# dainyuan.net
KiCad netlist of a schematic drawn in Altium Designer
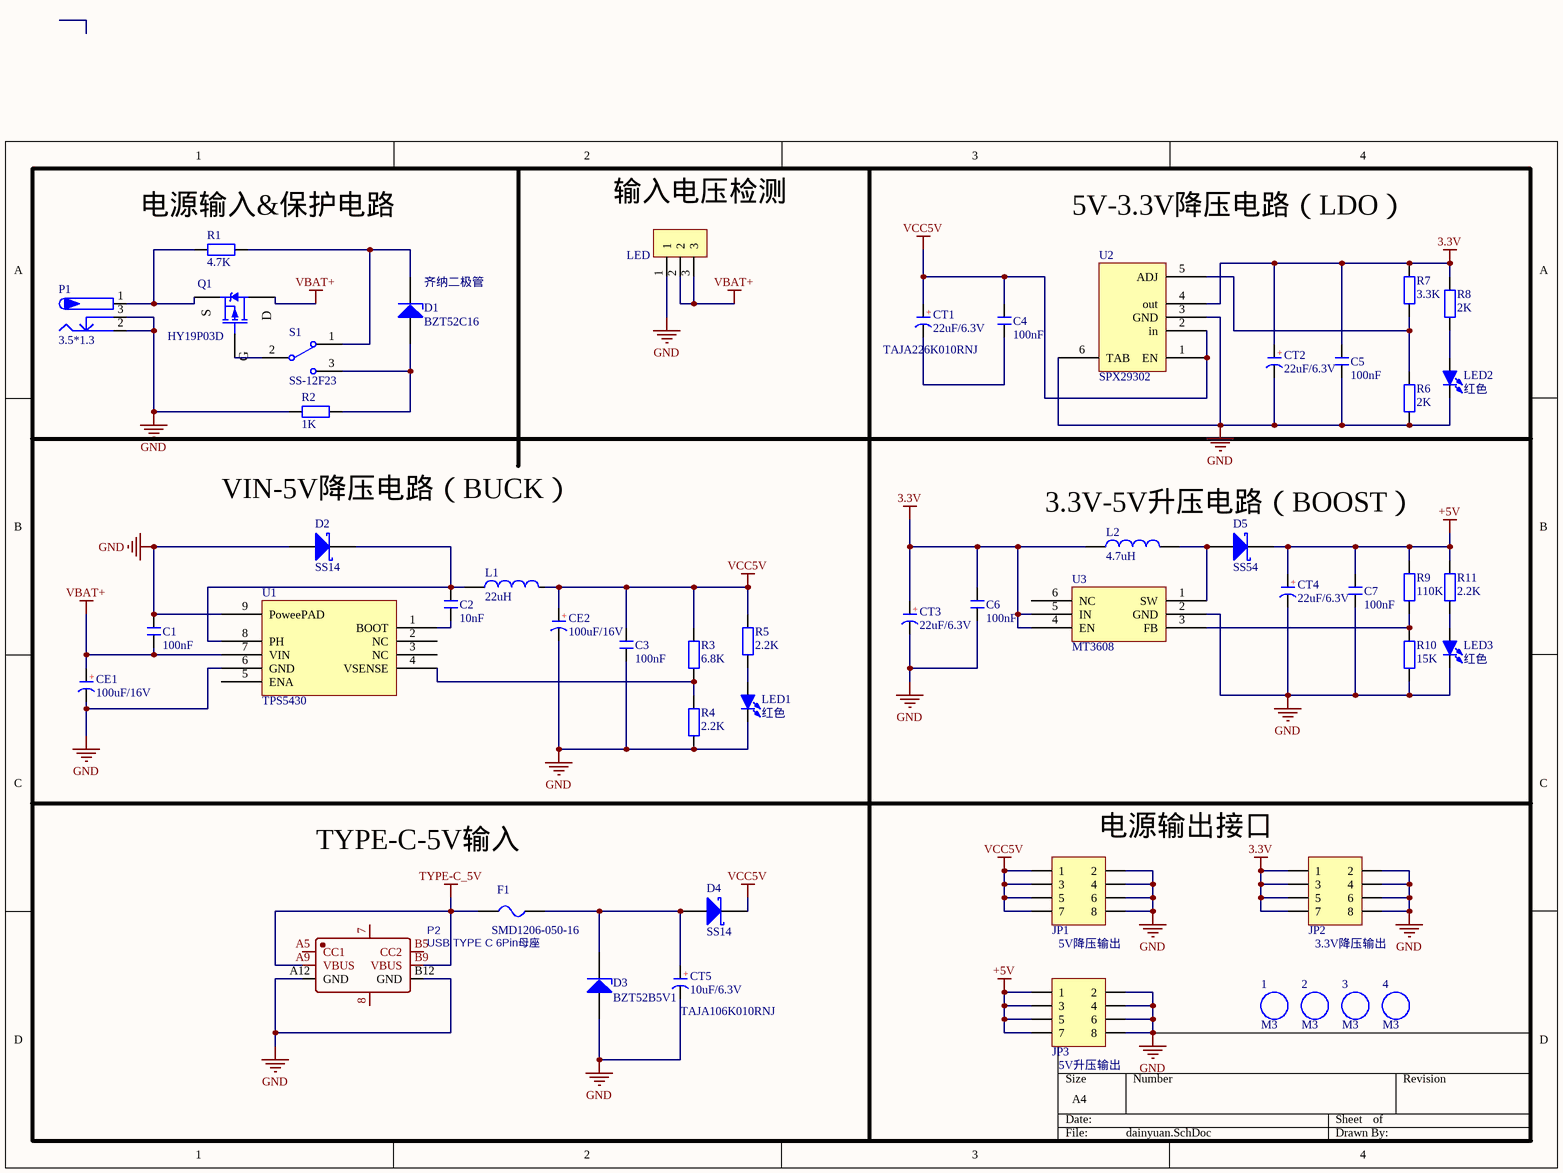
[diagram p0: dainyuan.SchDoc]

(export (version "E")
  (design (tool "Eeschema 10.0.6"))
  (components
    (comp (ref "1")
      (value "M3")
      (footprint "M3 125X200")
      (description "铜柱孔")
      (libsource (lib "0.7 - 常用按键-开关-蜂鸣器-电池") (part "M3"))
    )
    (comp (ref "2")
      (value "M3")
      (footprint "M3 125X200")
      (description "铜柱孔")
      (libsource (lib "0.7 - 常用按键-开关-蜂鸣器-电池") (part "M3"))
    )
    (comp (ref "3")
      (value "M3")
      (footprint "M3 125X200")
      (description "铜柱孔")
      (libsource (lib "0.7 - 常用按键-开关-蜂鸣器-电池") (part "M3"))
    )
    (comp (ref "4")
      (value "M3")
      (footprint "M3 125X200")
      (description "铜柱孔")
      (libsource (lib "0.7 - 常用按键-开关-蜂鸣器-电池") (part "M3"))
    )
    (comp (ref "C1")
      (value "100nF")
      (footprint "C 0805_L")
      (description "贴片电容")
      (libsource (lib "0.1 - 电阻-电容-电感") (part "C"))
    )
    (comp (ref "C2")
      (value "10nF")
      (footprint "C 0805_L")
      (description "贴片电容")
      (libsource (lib "0.1 - 电阻-电容-电感") (part "C"))
    )
    (comp (ref "C3")
      (value "100nF")
      (footprint "C 0805_L")
      (description "贴片电容")
      (libsource (lib "0.1 - 电阻-电容-电感") (part "C"))
    )
    (comp (ref "C4")
      (value "100nF")
      (footprint "C 0805_L")
      (description "贴片电容")
      (libsource (lib "0.1 - 电阻-电容-电感") (part "C"))
    )
    (comp (ref "C5")
      (value "100nF")
      (footprint "C 0805_L")
      (description "贴片电容")
      (libsource (lib "0.1 - 电阻-电容-电感") (part "C"))
    )
    (comp (ref "C6")
      (value "100nF")
      (footprint "C 0805_L")
      (description "贴片电容")
      (libsource (lib "0.1 - 电阻-电容-电感") (part "C"))
    )
    (comp (ref "C7")
      (value "100nF")
      (footprint "C 0805_L")
      (description "贴片电容")
      (libsource (lib "0.1 - 电阻-电容-电感") (part "C"))
    )
    (comp (ref "CE1")
      (value "100uF/16V")
      (footprint "CAP 3.5*8*11.5 - BK")
      (description "直插电解电容")
      (libsource (lib "0.1 - 电阻-电容-电感") (part "CE"))
    )
    (comp (ref "CE2")
      (value "100uF/16V")
      (footprint "CAP 3.5*8*11.5 - BK")
      (description "直插电解电容")
      (libsource (lib "0.1 - 电阻-电容-电感") (part "CE"))
    )
    (comp (ref "CT1")
      (value "22uF/6.3V")
      (footprint "CD A(3216)")
      (description "贴片钽电容")
      (libsource (lib "0.1 - 电阻-电容-电感") (part "CT"))
    )
    (comp (ref "CT2")
      (value "22uF/6.3V")
      (footprint "CD A(3216)")
      (description "贴片钽电容")
      (libsource (lib "0.1 - 电阻-电容-电感") (part "CT"))
    )
    (comp (ref "CT3")
      (value "22uF/6.3V")
      (footprint "CD A(3216)")
      (description "贴片钽电容")
      (libsource (lib "0.1 - 电阻-电容-电感") (part "CT"))
    )
    (comp (ref "CT4")
      (value "22uF/6.3V")
      (footprint "CD A(3216)")
      (description "贴片钽电容")
      (libsource (lib "0.1 - 电阻-电容-电感") (part "CT"))
    )
    (comp (ref "CT5")
      (value "10uF/6.3V")
      (footprint "CD A(3216)")
      (description "贴片钽电容")
      (libsource (lib "0.1 - 电阻-电容-电感") (part "CT"))
    )
    (comp (ref "D1")
      (value "BZT52C16")
      (footprint "SOD-123")
      (description "Zener Diode（齐纳）")
      (libsource (lib "0.2 - 二极管-整流桥") (part "稳压二极管"))
    )
    (comp (ref "D2")
      (value "SS14")
      (footprint "SMA")
      (description "肖特基二极管")
      (libsource (lib "0.2 - 二极管-整流桥") (part "SS14"))
    )
    (comp (ref "D3")
      (value "BZT52B5V1")
      (footprint "SOD-123")
      (description "Zener Diode")
      (libsource (lib "0.2 - 二极管-整流桥") (part "稳压二极管"))
    )
    (comp (ref "D4")
      (value "SS14")
      (footprint "SMA")
      (description "肖特基二极管")
      (libsource (lib "0.2 - 二极管-整流桥") (part "SS14"))
    )
    (comp (ref "D5")
      (value "SS54")
      (footprint "SMB")
      (description "肖特基二极管")
      (libsource (lib "0.2 - 二极管-整流桥") (part "SS54"))
    )
    (comp (ref "F1")
      (value "SMD1206-050-16")
      (footprint "FU 1206")
      (description "自恢复保险丝")
      (fields (field (name "版权归属") "封装库来自淘宝卖家 ID：黄晶宝石"))
      (libsource (lib "0.5 - 保险丝-晶振-光耦") (part "FU"))
    )
    (comp (ref "JP1")
      (value "Header 4X2")
      (footprint "HDR2.54-LI-2x4P")
      (description "4*2P接插件")
      (fields (field (name "版权归属") "封装库来自淘宝 ID：黄晶宝石"))
      (libsource (lib "5.4 - 接插件-脚距2.54 (100mil) ") (part "Header 4X2"))
    )
    (comp (ref "JP2")
      (value "Header 4X2")
      (footprint "HDR2.54-LI-2x4P")
      (description "4*2P接插件")
      (fields (field (name "版权归属") "封装库来自淘宝 ID：黄晶宝石"))
      (libsource (lib "5.4 - 接插件-脚距2.54 (100mil) ") (part "Header 4X2"))
    )
    (comp (ref "JP3")
      (value "Header 4X2")
      (footprint "HDR2.54-LI-2x4P")
      (description "4*2P接插件")
      (fields (field (name "版权归属") "封装库来自淘宝 ID：黄晶宝石"))
      (libsource (lib "5.4 - 接插件-脚距2.54 (100mil) ") (part "Header 4X2"))
    )
    (comp (ref "L1")
      (value "22uH")
      (footprint "L-SMD-0630")
      (description "小功率贴片电感")
      (libsource (lib "0.1 - 电阻-电容-电感") (part "L"))
    )
    (comp (ref "L2")
      (value "4.7uH")
      (footprint "L-SMD-0630")
      (description "小功率贴片电感")
      (libsource (lib "0.1 - 电阻-电容-电感") (part "L"))
    )
    (comp (ref "LED")
      (value "HDR-1X3")
      (footprint "HDR2.54-M-LI-3P")
      (description "3P接插件")
      (fields (field (name "版权归属") "封装库来自淘宝 ID：黄晶宝石"))
      (libsource (lib "5.4 - 接插件-脚距2.54 (100mil) ") (part "Header 3"))
    )
    (comp (ref "LED1")
      (value "红色")
      (footprint "LED 0805R")
      (description "贴片LED")
      (libsource (lib "0.3 - LED发光二极管") (part "LED-SMD"))
    )
    (comp (ref "LED2")
      (value "红色")
      (footprint "LED 0805R")
      (description "贴片LED")
      (libsource (lib "0.3 - LED发光二极管") (part "LED-SMD"))
    )
    (comp (ref "LED3")
      (value "红色")
      (footprint "LED 0805R")
      (description "贴片LED")
      (libsource (lib "0.3 - LED发光二极管") (part "LED-SMD"))
    )
    (comp (ref "P1")
      (value "3.5*1.3")
      (footprint "DC-005")
      (description "低压电源接口")
      (fields (field (name "版权归属") "封装库来自淘宝 ID：黄晶宝石"))
      (libsource (lib "0.8 - 以太网-音频-USB插座") (part "P-DC"))
    )
    (comp (ref "P2")
      (value "USB TYPE C 6Pin母座")
      (footprint "USB-C-SMD_10P-P1.00-L6.8-W8.9")
      (fields
        (field (name "BOM_SUPPLIER PART") "C381473")
        (field (name "BOM_MANUFACTURER PART") "TYC-252D-CB160")
        (field (name "CONTRIBUTOR") "LCSC")
      )
      (libsource (lib "0.8 - 以太网-音频-USB插座") (part "USB TYPE C 6Pin母座"))
    )
    (comp (ref "Q1")
      (value "HY19P03D")
      (footprint "TO252 - 3")
      (description "P沟场效应管")
      (libsource (lib "0.4 - 三极管-场效应管-可控硅") (part "IRF540"))
    )
    (comp (ref "R1")
      (value "4.7K")
      (footprint "R 0805_L")
      (description "贴片电阻")
      (libsource (lib "0.1 - 电阻-电容-电感") (part "R"))
    )
    (comp (ref "R2")
      (value "1K")
      (footprint "R 0805_L")
      (description "贴片电阻")
      (libsource (lib "0.1 - 电阻-电容-电感") (part "R"))
    )
    (comp (ref "R3")
      (value "6.8K")
      (footprint "R 0805_L")
      (description "贴片电阻")
      (libsource (lib "0.1 - 电阻-电容-电感") (part "R"))
    )
    (comp (ref "R4")
      (value "2.2K")
      (footprint "R 0805_L")
      (description "贴片电阻")
      (libsource (lib "0.1 - 电阻-电容-电感") (part "R"))
    )
    (comp (ref "R5")
      (value "2.2K")
      (footprint "R 0805_L")
      (description "贴片电阻")
      (libsource (lib "0.1 - 电阻-电容-电感") (part "R"))
    )
    (comp (ref "R6")
      (value "2K")
      (footprint "R 0805_L")
      (description "贴片电阻")
      (libsource (lib "0.1 - 电阻-电容-电感") (part "R"))
    )
    (comp (ref "R7")
      (value "3.3K")
      (footprint "R 0805_L")
      (description "贴片电阻")
      (libsource (lib "0.1 - 电阻-电容-电感") (part "R"))
    )
    (comp (ref "R8")
      (value "2K")
      (footprint "R 0805_L")
      (description "贴片电阻")
      (libsource (lib "0.1 - 电阻-电容-电感") (part "R"))
    )
    (comp (ref "R9")
      (value "110K")
      (footprint "R 0805_L")
      (description "贴片电阻")
      (libsource (lib "0.1 - 电阻-电容-电感") (part "R"))
    )
    (comp (ref "R10")
      (value "15K")
      (footprint "R 0805_L")
      (description "贴片电阻")
      (libsource (lib "0.1 - 电阻-电容-电感") (part "R"))
    )
    (comp (ref "R11")
      (value "2.2K")
      (footprint "R 0805_L")
      (description "贴片电阻")
      (libsource (lib "0.1 - 电阻-电容-电感") (part "R"))
    )
    (comp (ref "S1")
      (value "SS-12F23")
      (footprint "SS-12D10")
      (description "1路波动开关")
      (fields (field (name "版权归属") "封装库来自淘宝 ID：黄晶宝石"))
      (libsource (lib "0.7 - 常用按键-开关-蜂鸣器-电池") (part "SSW-1P"))
    )
    (comp (ref "U1")
      (value "TPS5430")
      (footprint "SOIC-8_EP")
      (description "DC可调降压")
      (libsource (lib "1.1 - 电源类芯片") (part "TPS5430"))
    )
    (comp (ref "U2")
      (value "SPX29302")
      (footprint "TO263-5")
      (description "LDO线性稳压芯片")
      (libsource (lib "1.1 - 电源类芯片") (part "SPX29302"))
    )
    (comp (ref "U3")
      (value "MT3608")
      (footprint "SOT23-6")
      (description "DC升压芯片")
      (libsource (lib "1.1 - 电源类芯片") (part "MT3608"))
    )
  )
  (nets
    (net (code "1") (name "+5V") (class "Default")
      (node (ref "C7") (pin "2") (pinfunction "2_2") (pintype "passive"))
      (node (ref "CT4") (pin "1") (pinfunction "A_1") (pintype "passive"))
      (node (ref "D5") (pin "2") (pinfunction "K_2") (pintype "passive"))
      (node (ref "JP3") (pin "1") (pinfunction "1_1") (pintype "passive"))
      (node (ref "JP3") (pin "3") (pinfunction "3_3") (pintype "passive"))
      (node (ref "JP3") (pin "5") (pinfunction "5_5") (pintype "passive"))
      (node (ref "JP3") (pin "7") (pinfunction "7_7") (pintype "passive"))
      (node (ref "R11") (pin "2") (pinfunction "2_2") (pintype "passive"))
      (node (ref "R9") (pin "2") (pinfunction "2_2") (pintype "passive"))
    )
    (net (code "2") (name "3.3V") (class "Default")
      (node (ref "C5") (pin "2") (pinfunction "2_2") (pintype "passive"))
      (node (ref "C6") (pin "2") (pinfunction "2_2") (pintype "passive"))
      (node (ref "CT2") (pin "1") (pinfunction "A_1") (pintype "passive"))
      (node (ref "CT3") (pin "1") (pinfunction "A_1") (pintype "passive"))
      (node (ref "JP2") (pin "1") (pinfunction "1_1") (pintype "passive"))
      (node (ref "JP2") (pin "3") (pinfunction "3_3") (pintype "passive"))
      (node (ref "JP2") (pin "5") (pinfunction "5_5") (pintype "passive"))
      (node (ref "JP2") (pin "7") (pinfunction "7_7") (pintype "passive"))
      (node (ref "L2") (pin "1") (pinfunction "1_1") (pintype "passive"))
      (node (ref "R7") (pin "2") (pinfunction "2_2") (pintype "passive"))
      (node (ref "R8") (pin "2") (pinfunction "2_2") (pintype "passive"))
      (node (ref "U2") (pin "4") (pinfunction "out_4") (pintype "passive"))
      (node (ref "U3") (pin "4") (pinfunction "EN_4") (pintype "passive"))
      (node (ref "U3") (pin "5") (pinfunction "IN_5") (pintype "passive"))
    )
    (net (code "3") (name "GND") (class "Default")
      (node (ref "C1") (pin "2") (pinfunction "2_2") (pintype "passive"))
      (node (ref "C3") (pin "1") (pinfunction "1_1") (pintype "passive"))
      (node (ref "C5") (pin "1") (pinfunction "1_1") (pintype "passive"))
      (node (ref "C6") (pin "1") (pinfunction "1_1") (pintype "passive"))
      (node (ref "C7") (pin "1") (pinfunction "1_1") (pintype "passive"))
      (node (ref "CE1") (pin "2") (pinfunction "K_2") (pintype "passive"))
      (node (ref "CE2") (pin "2") (pinfunction "K_2") (pintype "passive"))
      (node (ref "CT2") (pin "2") (pinfunction "K_2") (pintype "passive"))
      (node (ref "CT3") (pin "2") (pinfunction "K_2") (pintype "passive"))
      (node (ref "CT4") (pin "2") (pinfunction "K_2") (pintype "passive"))
      (node (ref "CT5") (pin "2") (pinfunction "K_2") (pintype "passive"))
      (node (ref "D2") (pin "1") (pinfunction "A_1") (pintype "passive"))
      (node (ref "D3") (pin "1") (pinfunction "A_1") (pintype "passive"))
      (node (ref "JP1") (pin "2") (pinfunction "2_2") (pintype "passive"))
      (node (ref "JP1") (pin "4") (pinfunction "4_4") (pintype "passive"))
      (node (ref "JP1") (pin "6") (pinfunction "6_6") (pintype "passive"))
      (node (ref "JP1") (pin "8") (pinfunction "8_8") (pintype "passive"))
      (node (ref "JP2") (pin "2") (pinfunction "2_2") (pintype "passive"))
      (node (ref "JP2") (pin "4") (pinfunction "4_4") (pintype "passive"))
      (node (ref "JP2") (pin "6") (pinfunction "6_6") (pintype "passive"))
      (node (ref "JP2") (pin "8") (pinfunction "8_8") (pintype "passive"))
      (node (ref "JP3") (pin "2") (pinfunction "2_2") (pintype "passive"))
      (node (ref "JP3") (pin "4") (pinfunction "4_4") (pintype "passive"))
      (node (ref "JP3") (pin "6") (pinfunction "6_6") (pintype "passive"))
      (node (ref "JP3") (pin "8") (pinfunction "8_8") (pintype "passive"))
      (node (ref "LED") (pin "1") (pinfunction "1_1") (pintype "passive"))
      (node (ref "LED1") (pin "2") (pinfunction "K_2") (pintype "passive"))
      (node (ref "LED2") (pin "2") (pinfunction "K_2") (pintype "passive"))
      (node (ref "LED3") (pin "2") (pinfunction "K_2") (pintype "passive"))
      (node (ref "P1") (pin "2") (pintype "power_in"))
      (node (ref "P1") (pin "3") (pintype "power_in"))
      (node (ref "P2") (pin "A12") (pinfunction "GND_A12") (pintype "passive"))
      (node (ref "P2") (pin "B12") (pinfunction "GND_B12") (pintype "passive"))
      (node (ref "R10") (pin "1") (pinfunction "1_1") (pintype "passive"))
      (node (ref "R2") (pin "1") (pinfunction "1_1") (pintype "passive"))
      (node (ref "R4") (pin "1") (pinfunction "1_1") (pintype "passive"))
      (node (ref "R6") (pin "1") (pinfunction "1_1") (pintype "passive"))
      (node (ref "U1") (pin "6") (pinfunction "GND_6") (pintype "passive"))
      (node (ref "U1") (pin "9") (pinfunction "PoweePAD_9") (pintype "passive"))
      (node (ref "U2") (pin "3") (pinfunction "GND_3") (pintype "passive"))
      (node (ref "U2") (pin "6") (pinfunction "TAB_6") (pintype "passive"))
      (node (ref "U3") (pin "2") (pinfunction "GND_2") (pintype "passive"))
    )
    (net (code "4") (name "Net-(CT1-K)") (class "Default")
      (node (ref "C4") (pin "1") (pinfunction "1_1") (pintype "passive"))
      (node (ref "CT1") (pin "2") (pinfunction "K_2") (pintype "passive"))
    )
    (net (code "5") (name "Net-(CT5-A)") (class "Default")
      (node (ref "CT5") (pin "1") (pinfunction "A_1") (pintype "passive"))
      (node (ref "D3") (pin "2") (pinfunction "K_2") (pintype "passive"))
      (node (ref "D4") (pin "1") (pinfunction "A_1") (pintype "passive"))
      (node (ref "F1") (pin "2") (pinfunction "2_2") (pintype "passive"))
    )
    (net (code "6") (name "Net-(D1-A)") (class "Default")
      (node (ref "D1") (pin "1") (pinfunction "A_1") (pintype "passive"))
      (node (ref "R2") (pin "2") (pinfunction "2_2") (pintype "passive"))
      (node (ref "S1") (pin "3") (pinfunction "3_3") (pintype "passive"))
    )
    (net (code "7") (name "Net-(D1-K)") (class "Default")
      (node (ref "D1") (pin "2") (pinfunction "K_2") (pintype "passive"))
      (node (ref "R1") (pin "2") (pinfunction "2_2") (pintype "passive"))
      (node (ref "S1") (pin "1") (pinfunction "1_1") (pintype "passive"))
    )
    (net (code "8") (name "Net-(D2-K)") (class "Default")
      (node (ref "C2") (pin "2") (pinfunction "2_2") (pintype "passive"))
      (node (ref "D2") (pin "2") (pinfunction "K_2") (pintype "passive"))
      (node (ref "L1") (pin "1") (pinfunction "1_1") (pintype "passive"))
      (node (ref "U1") (pin "8") (pinfunction "PH_8") (pintype "passive"))
    )
    (net (code "9") (name "Net-(D5-A)") (class "Default")
      (node (ref "D5") (pin "1") (pinfunction "A_1") (pintype "passive"))
      (node (ref "L2") (pin "2") (pinfunction "2_2") (pintype "passive"))
      (node (ref "U3") (pin "1") (pinfunction "SW_1") (pintype "passive"))
    )
    (net (code "10") (name "Net-(LED1-A)") (class "Default")
      (node (ref "LED1") (pin "1") (pinfunction "A_1") (pintype "passive"))
      (node (ref "R5") (pin "1") (pinfunction "1_1") (pintype "passive"))
    )
    (net (code "11") (name "Net-(LED2-A)") (class "Default")
      (node (ref "LED2") (pin "1") (pinfunction "A_1") (pintype "passive"))
      (node (ref "R8") (pin "1") (pinfunction "1_1") (pintype "passive"))
    )
    (net (code "12") (name "Net-(LED3-A)") (class "Default")
      (node (ref "LED3") (pin "1") (pinfunction "A_1") (pintype "passive"))
      (node (ref "R11") (pin "1") (pinfunction "1_1") (pintype "passive"))
    )
    (net (code "13") (name "Net-(Q1-G)") (class "Default")
      (node (ref "Q1") (pin "1") (pinfunction "G_1") (pintype "passive"))
      (node (ref "S1") (pin "2") (pinfunction "2_2") (pintype "passive"))
    )
    (net (code "14") (name "Net-(Q1-S)") (class "Default")
      (node (ref "P1") (pin "1") (pintype "power_in"))
      (node (ref "Q1") (pin "3") (pinfunction "S_3") (pintype "passive"))
      (node (ref "R1") (pin "1") (pinfunction "1_1") (pintype "passive"))
    )
    (net (code "15") (name "Net-(U1-BOOT)") (class "Default")
      (node (ref "C2") (pin "1") (pinfunction "1_1") (pintype "passive"))
      (node (ref "U1") (pin "1") (pinfunction "BOOT_1") (pintype "passive"))
    )
    (net (code "16") (name "Net-(U1-VSENSE)") (class "Default")
      (node (ref "R3") (pin "1") (pinfunction "1_1") (pintype "passive"))
      (node (ref "R4") (pin "2") (pinfunction "2_2") (pintype "passive"))
      (node (ref "U1") (pin "4") (pinfunction "VSENSE_4") (pintype "passive"))
    )
    (net (code "17") (name "Net-(U2-ADJ)") (class "Default")
      (node (ref "R6") (pin "2") (pinfunction "2_2") (pintype "passive"))
      (node (ref "R7") (pin "1") (pinfunction "1_1") (pintype "passive"))
      (node (ref "U2") (pin "5") (pinfunction "ADJ_5") (pintype "passive"))
    )
    (net (code "18") (name "Net-(U3-FB)") (class "Default")
      (node (ref "R10") (pin "2") (pinfunction "2_2") (pintype "passive"))
      (node (ref "R9") (pin "1") (pinfunction "1_1") (pintype "passive"))
      (node (ref "U3") (pin "3") (pinfunction "FB_3") (pintype "passive"))
    )
    (net (code "19") (name "TYPE-C_5V") (class "Default")
      (node (ref "F1") (pin "1") (pinfunction "1_1") (pintype "passive"))
      (node (ref "P2") (pin "A9") (pinfunction "VBUS_A9") (pintype "passive"))
      (node (ref "P2") (pin "B9") (pinfunction "VBUS_B9") (pintype "passive"))
    )
    (net (code "20") (name "VBAT+") (class "Default")
      (node (ref "C1") (pin "1") (pinfunction "1_1") (pintype "passive"))
      (node (ref "CE1") (pin "1") (pinfunction "A_1") (pintype "passive"))
      (node (ref "LED") (pin "2") (pinfunction "2_2") (pintype "passive"))
      (node (ref "LED") (pin "3") (pinfunction "3_3") (pintype "passive"))
      (node (ref "Q1") (pin "2") (pinfunction "D_2") (pintype "passive"))
      (node (ref "U1") (pin "7") (pinfunction "VIN_7") (pintype "passive"))
    )
    (net (code "21") (name "VCC5V") (class "Default")
      (node (ref "C3") (pin "2") (pinfunction "2_2") (pintype "passive"))
      (node (ref "C4") (pin "2") (pinfunction "2_2") (pintype "passive"))
      (node (ref "CE2") (pin "1") (pinfunction "A_1") (pintype "passive"))
      (node (ref "CT1") (pin "1") (pinfunction "A_1") (pintype "passive"))
      (node (ref "D4") (pin "2") (pinfunction "K_2") (pintype "passive"))
      (node (ref "JP1") (pin "1") (pinfunction "1_1") (pintype "passive"))
      (node (ref "JP1") (pin "3") (pinfunction "3_3") (pintype "passive"))
      (node (ref "JP1") (pin "5") (pinfunction "5_5") (pintype "passive"))
      (node (ref "JP1") (pin "7") (pinfunction "7_7") (pintype "passive"))
      (node (ref "L1") (pin "2") (pinfunction "2_2") (pintype "passive"))
      (node (ref "R3") (pin "2") (pinfunction "2_2") (pintype "passive"))
      (node (ref "R5") (pin "2") (pinfunction "2_2") (pintype "passive"))
      (node (ref "U2") (pin "1") (pinfunction "EN_1") (pintype "passive"))
      (node (ref "U2") (pin "2") (pinfunction "in_2") (pintype "passive"))
    )
    (net (code "22") (name "unconnected-(P2-CC1-PadA5)") (class "Default")
      (node (ref "P2") (pin "A5") (pinfunction "CC1_A5") (pintype "passive"))
    )
    (net (code "23") (name "unconnected-(P2-CC2-PadB5)") (class "Default")
      (node (ref "P2") (pin "B5") (pinfunction "CC2_B5") (pintype "passive"))
    )
    (net (code "24") (name "unconnected-(P2-Pad7)") (class "Default")
      (node (ref "P2") (pin "7") (pinfunction "7_7") (pintype "passive"))
    )
    (net (code "25") (name "unconnected-(P2-Pad8)") (class "Default")
      (node (ref "P2") (pin "8") (pinfunction "8_8") (pintype "passive"))
    )
    (net (code "26") (name "unconnected-(U1-ENA-Pad5)") (class "Default")
      (node (ref "U1") (pin "5") (pinfunction "ENA_5") (pintype "passive"))
    )
    (net (code "27") (name "unconnected-(U1-NC-Pad2)") (class "Default")
      (node (ref "U1") (pin "2") (pinfunction "NC_2") (pintype "passive"))
    )
    (net (code "28") (name "unconnected-(U1-NC-Pad3)") (class "Default")
      (node (ref "U1") (pin "3") (pinfunction "NC_3") (pintype "passive"))
    )
    (net (code "29") (name "unconnected-(U3-NC-Pad6)") (class "Default")
      (node (ref "U3") (pin "6") (pinfunction "NC_6") (pintype "passive"))
    )
  )
)
